# MAKER-UNO-X.net
KiCad netlist of a schematic drawn in EAGLE
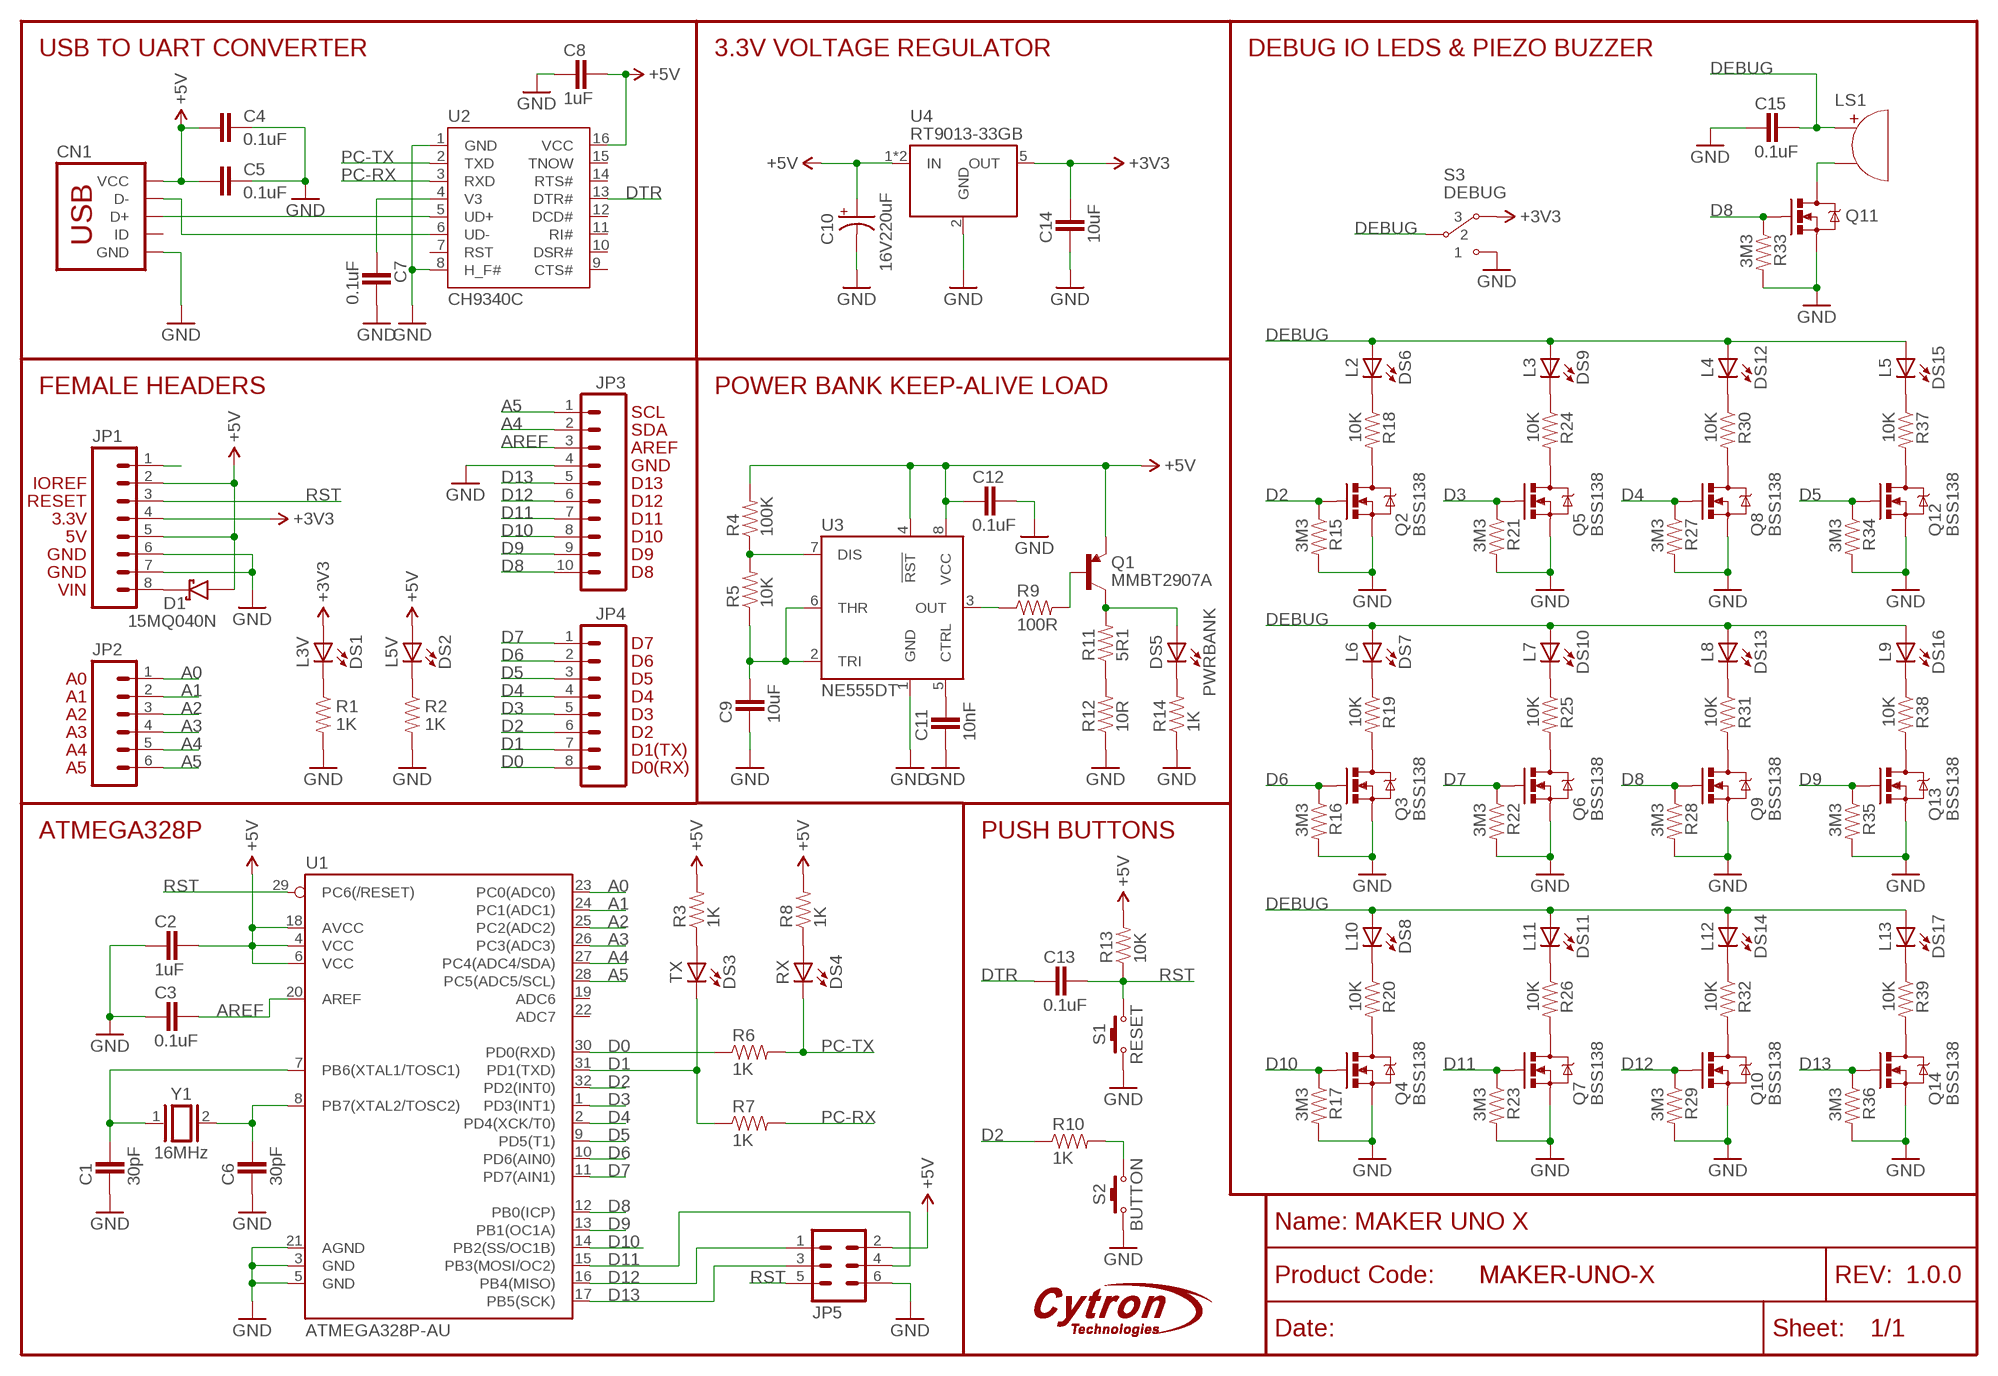
[diagram p0: schematic, sheet 1]

(export (version "E")
  (design (tool "Eeschema 10.0.6"))
  (components
    (comp (ref "C1")
      (value "30pF")
      (footprint "eagle-import:1608")
      (libsource (lib "eagle-import") (part "CAP-C_(1608)_30PF"))
    )
    (comp (ref "C2")
      (value "1uF")
      (footprint "eagle-import:1608")
      (libsource (lib "eagle-import") (part "CAP-C_(1608)_1UF"))
    )
    (comp (ref "C3")
      (value "0.1uF")
      (footprint "eagle-import:1608")
      (libsource (lib "eagle-import") (part "CAP-C_(1608)_0.1UF"))
    )
    (comp (ref "C4")
      (value "0.1uF")
      (footprint "eagle-import:1608")
      (libsource (lib "eagle-import") (part "CAP-C_(1608)_0.1UF"))
    )
    (comp (ref "C5")
      (value "0.1uF")
      (footprint "eagle-import:1608")
      (libsource (lib "eagle-import") (part "CAP-C_(1608)_0.1UF"))
    )
    (comp (ref "C6")
      (value "30pF")
      (footprint "eagle-import:1608")
      (libsource (lib "eagle-import") (part "CAP-C_(1608)_30PF"))
    )
    (comp (ref "C7")
      (value "0.1uF")
      (footprint "eagle-import:1608")
      (libsource (lib "eagle-import") (part "CAP-C_(1608)_0.1UF"))
    )
    (comp (ref "C8")
      (value "1uF")
      (footprint "eagle-import:1608")
      (libsource (lib "eagle-import") (part "CAP-C_(1608)_1UF"))
    )
    (comp (ref "C9")
      (value "10uF")
      (footprint "eagle-import:2012")
      (libsource (lib "eagle-import") (part "CAP-C_(2012)_10UF"))
    )
    (comp (ref "C10")
      (value "16V220uF")
      (footprint "eagle-import:ECAP-CHEMICON-F")
      (libsource (lib "eagle-import") (part "CAP-E-ALUMINIUM_(CHEMICON-F55)_16V220UF"))
    )
    (comp (ref "C11")
      (value "10nF")
      (footprint "eagle-import:1608")
      (libsource (lib "eagle-import") (part "CAP-C_(1608)_10NF"))
    )
    (comp (ref "C12")
      (value "0.1uF")
      (footprint "eagle-import:1608")
      (libsource (lib "eagle-import") (part "CAP-C_(1608)_0.1UF"))
    )
    (comp (ref "C13")
      (value "0.1uF")
      (footprint "eagle-import:1608")
      (libsource (lib "eagle-import") (part "CAP-C_(1608)_0.1UF"))
    )
    (comp (ref "C14")
      (value "10uF")
      (footprint "eagle-import:2012")
      (libsource (lib "eagle-import") (part "CAP-C_(2012)_10UF"))
    )
    (comp (ref "C15")
      (value "0.1uF")
      (footprint "eagle-import:1608")
      (libsource (lib "eagle-import") (part "CAP-C_(1608)_0.1UF"))
    )
    (comp (ref "CN1")
      (value "USB-5PIN_(MICRO-B-RA)")
      (footprint "eagle-import:USB-MICRO-B-REC")
      (libsource (lib "eagle-import") (part "USB-5PIN_(MICRO-B-RA)"))
    )
    (comp (ref "D1")
      (value "40V 3A")
      (footprint "eagle-import:D-SMA")
      (fields (field (name "MPN") "15MQ040N"))
      (libsource (lib "eagle-import") (part "DIODE-SCHOTTKY_(SMA)_15MQ040N"))
    )
    (comp (ref "DS1")
      (value "Green")
      (footprint "eagle-import:LED-1608")
      (fields (field (name "LABEL") "L3V"))
      (libsource (lib "eagle-import") (part "LED_(1608)_GREEN"))
    )
    (comp (ref "DS2")
      (value "Green")
      (footprint "eagle-import:LED-1608")
      (fields (field (name "LABEL") "L5V"))
      (libsource (lib "eagle-import") (part "LED_(1608)_GREEN"))
    )
    (comp (ref "DS3")
      (value "Red")
      (footprint "eagle-import:LED-1608")
      (fields (field (name "LABEL") "TX"))
      (libsource (lib "eagle-import") (part "LED_(1608)_RED"))
    )
    (comp (ref "DS4")
      (value "Yellow")
      (footprint "eagle-import:LED-1608")
      (fields (field (name "LABEL") "RX"))
      (libsource (lib "eagle-import") (part "LED_(1608)_YELLOW"))
    )
    (comp (ref "DS5")
      (value "Red")
      (footprint "eagle-import:LED-1608")
      (fields (field (name "LABEL") "PWRBANK"))
      (libsource (lib "eagle-import") (part "LED_(1608)_RED"))
    )
    (comp (ref "DS6")
      (value "Blue")
      (footprint "eagle-import:LED-1608")
      (fields (field (name "LABEL") "L2"))
      (libsource (lib "eagle-import") (part "LED_(1608)_BLUE"))
    )
    (comp (ref "DS7")
      (value "Blue")
      (footprint "eagle-import:LED-1608")
      (fields (field (name "LABEL") "L6"))
      (libsource (lib "eagle-import") (part "LED_(1608)_BLUE"))
    )
    (comp (ref "DS8")
      (value "Blue")
      (footprint "eagle-import:LED-1608")
      (fields (field (name "LABEL") "L10"))
      (libsource (lib "eagle-import") (part "LED_(1608)_BLUE"))
    )
    (comp (ref "DS9")
      (value "Blue")
      (footprint "eagle-import:LED-1608")
      (fields (field (name "LABEL") "L3"))
      (libsource (lib "eagle-import") (part "LED_(1608)_BLUE"))
    )
    (comp (ref "DS10")
      (value "Blue")
      (footprint "eagle-import:LED-1608")
      (fields (field (name "LABEL") "L7"))
      (libsource (lib "eagle-import") (part "LED_(1608)_BLUE"))
    )
    (comp (ref "DS11")
      (value "Blue")
      (footprint "eagle-import:LED-1608")
      (fields (field (name "LABEL") "L11"))
      (libsource (lib "eagle-import") (part "LED_(1608)_BLUE"))
    )
    (comp (ref "DS12")
      (value "Blue")
      (footprint "eagle-import:LED-1608")
      (fields (field (name "LABEL") "L4"))
      (libsource (lib "eagle-import") (part "LED_(1608)_BLUE"))
    )
    (comp (ref "DS13")
      (value "Blue")
      (footprint "eagle-import:LED-1608")
      (fields (field (name "LABEL") "L8"))
      (libsource (lib "eagle-import") (part "LED_(1608)_BLUE"))
    )
    (comp (ref "DS14")
      (value "Blue")
      (footprint "eagle-import:LED-1608")
      (fields (field (name "LABEL") "L12"))
      (libsource (lib "eagle-import") (part "LED_(1608)_BLUE"))
    )
    (comp (ref "DS15")
      (value "Blue")
      (footprint "eagle-import:LED-1608")
      (fields (field (name "LABEL") "L5"))
      (libsource (lib "eagle-import") (part "LED_(1608)_BLUE"))
    )
    (comp (ref "DS16")
      (value "Blue")
      (footprint "eagle-import:LED-1608")
      (fields (field (name "LABEL") "L9"))
      (libsource (lib "eagle-import") (part "LED_(1608)_BLUE"))
    )
    (comp (ref "DS17")
      (value "Blue")
      (footprint "eagle-import:LED-1608")
      (fields (field (name "LABEL") "L13"))
      (libsource (lib "eagle-import") (part "LED_(1608)_BLUE"))
    )
    (comp (ref "JP1")
      (value "8 Ways")
      (footprint "eagle-import:S-HDR-F1X08")
      (libsource (lib "eagle-import") (part "HEADER-1X08_(SMD-FEMALE-TYPE1)"))
    )
    (comp (ref "JP2")
      (value "6 Ways")
      (footprint "eagle-import:S-HDR-F1X06")
      (libsource (lib "eagle-import") (part "HEADER-1X06_(SMD-FEMALE-TYPE1)"))
    )
    (comp (ref "JP3")
      (value "10 Ways")
      (footprint "eagle-import:S-HDR-F1X10")
      (libsource (lib "eagle-import") (part "HEADER-1X10_(SMD-FEMALE-TYPE1)"))
    )
    (comp (ref "JP4")
      (value "8 Ways")
      (footprint "eagle-import:S-HDR-F1X08")
      (libsource (lib "eagle-import") (part "HEADER-1X08_(SMD-FEMALE-TYPE1)"))
    )
    (comp (ref "JP5")
      (value "2x3 Ways")
      (footprint "eagle-import:S-HDR-M2X03")
      (libsource (lib "eagle-import") (part "HEADER-2X03_(S-HDR-M2X03)"))
    )
    (comp (ref "LS1")
      (value "BUZZER_(8530)")
      (footprint "eagle-import:S-BUZZER-HXD-8530A-03627")
      (libsource (lib "eagle-import") (part "BUZZER_(8530)"))
    )
    (comp (ref "Q1")
      (value "60V 600mA")
      (footprint "eagle-import:SOT-23")
      (fields (field (name "MF") "CHANGJIANG") (field (name "MPN") "MMBT2907A"))
      (libsource (lib "eagle-import") (part "TRANSISTOR-PNP_(SOT-23-BEC)_MMBT2907"))
    )
    (comp (ref "Q2")
      (value "50V 220mA")
      (footprint "eagle-import:SOT-23")
      (fields (field (name "MPN") "BSS138"))
      (libsource (lib "eagle-import") (part "MOSFET-N_(SOT-23)_BSS138"))
    )
    (comp (ref "Q3")
      (value "50V 220mA")
      (footprint "eagle-import:SOT-23")
      (fields (field (name "MPN") "BSS138"))
      (libsource (lib "eagle-import") (part "MOSFET-N_(SOT-23)_BSS138"))
    )
    (comp (ref "Q4")
      (value "50V 220mA")
      (footprint "eagle-import:SOT-23")
      (fields (field (name "MPN") "BSS138"))
      (libsource (lib "eagle-import") (part "MOSFET-N_(SOT-23)_BSS138"))
    )
    (comp (ref "Q5")
      (value "50V 220mA")
      (footprint "eagle-import:SOT-23")
      (fields (field (name "MPN") "BSS138"))
      (libsource (lib "eagle-import") (part "MOSFET-N_(SOT-23)_BSS138"))
    )
    (comp (ref "Q6")
      (value "50V 220mA")
      (footprint "eagle-import:SOT-23")
      (fields (field (name "MPN") "BSS138"))
      (libsource (lib "eagle-import") (part "MOSFET-N_(SOT-23)_BSS138"))
    )
    (comp (ref "Q7")
      (value "50V 220mA")
      (footprint "eagle-import:SOT-23")
      (fields (field (name "MPN") "BSS138"))
      (libsource (lib "eagle-import") (part "MOSFET-N_(SOT-23)_BSS138"))
    )
    (comp (ref "Q8")
      (value "50V 220mA")
      (footprint "eagle-import:SOT-23")
      (fields (field (name "MPN") "BSS138"))
      (libsource (lib "eagle-import") (part "MOSFET-N_(SOT-23)_BSS138"))
    )
    (comp (ref "Q9")
      (value "50V 220mA")
      (footprint "eagle-import:SOT-23")
      (fields (field (name "MPN") "BSS138"))
      (libsource (lib "eagle-import") (part "MOSFET-N_(SOT-23)_BSS138"))
    )
    (comp (ref "Q10")
      (value "50V 220mA")
      (footprint "eagle-import:SOT-23")
      (fields (field (name "MPN") "BSS138"))
      (libsource (lib "eagle-import") (part "MOSFET-N_(SOT-23)_BSS138"))
    )
    (comp (ref "Q11")
      (value "50V 220mA")
      (footprint "eagle-import:SOT-23")
      (fields (field (name "MPN") "BSS138"))
      (libsource (lib "eagle-import") (part "MOSFET-N_(SOT-23)_BSS138"))
    )
    (comp (ref "Q12")
      (value "50V 220mA")
      (footprint "eagle-import:SOT-23")
      (fields (field (name "MPN") "BSS138"))
      (libsource (lib "eagle-import") (part "MOSFET-N_(SOT-23)_BSS138"))
    )
    (comp (ref "Q13")
      (value "50V 220mA")
      (footprint "eagle-import:SOT-23")
      (fields (field (name "MPN") "BSS138"))
      (libsource (lib "eagle-import") (part "MOSFET-N_(SOT-23)_BSS138"))
    )
    (comp (ref "Q14")
      (value "50V 220mA")
      (footprint "eagle-import:SOT-23")
      (fields (field (name "MPN") "BSS138"))
      (libsource (lib "eagle-import") (part "MOSFET-N_(SOT-23)_BSS138"))
    )
    (comp (ref "R1")
      (value "1K")
      (footprint "eagle-import:1608")
      (libsource (lib "eagle-import") (part "RESISTOR_(1608)_1K"))
    )
    (comp (ref "R2")
      (value "1K")
      (footprint "eagle-import:1608")
      (libsource (lib "eagle-import") (part "RESISTOR_(1608)_1K"))
    )
    (comp (ref "R3")
      (value "1K")
      (footprint "eagle-import:1608")
      (libsource (lib "eagle-import") (part "RESISTOR_(1608)_1K"))
    )
    (comp (ref "R4")
      (value "100K")
      (footprint "eagle-import:1608")
      (libsource (lib "eagle-import") (part "RESISTOR_(1608)_100K"))
    )
    (comp (ref "R5")
      (value "10K")
      (footprint "eagle-import:1608")
      (libsource (lib "eagle-import") (part "RESISTOR_(1608)_10K"))
    )
    (comp (ref "R6")
      (value "1K")
      (footprint "eagle-import:1608")
      (libsource (lib "eagle-import") (part "RESISTOR_(1608)_1K"))
    )
    (comp (ref "R7")
      (value "1K")
      (footprint "eagle-import:1608")
      (libsource (lib "eagle-import") (part "RESISTOR_(1608)_1K"))
    )
    (comp (ref "R8")
      (value "1K")
      (footprint "eagle-import:1608")
      (libsource (lib "eagle-import") (part "RESISTOR_(1608)_1K"))
    )
    (comp (ref "R9")
      (value "100R")
      (footprint "eagle-import:1608")
      (libsource (lib "eagle-import") (part "RESISTOR_(1608)_100R"))
    )
    (comp (ref "R10")
      (value "1K")
      (footprint "eagle-import:1608")
      (libsource (lib "eagle-import") (part "RESISTOR_(1608)_1K"))
    )
    (comp (ref "R11")
      (value "5R1")
      (footprint "eagle-import:2012")
      (libsource (lib "eagle-import") (part "RESISTOR_(2012)_5R1"))
    )
    (comp (ref "R12")
      (value "10R")
      (footprint "eagle-import:2012")
      (libsource (lib "eagle-import") (part "RESISTOR_(2012)_10R"))
    )
    (comp (ref "R13")
      (value "10K")
      (footprint "eagle-import:1608")
      (libsource (lib "eagle-import") (part "RESISTOR_(1608)_10K"))
    )
    (comp (ref "R14")
      (value "1K")
      (footprint "eagle-import:1608")
      (libsource (lib "eagle-import") (part "RESISTOR_(1608)_1K"))
    )
    (comp (ref "R15")
      (value "3M3")
      (footprint "eagle-import:1608")
      (libsource (lib "eagle-import") (part "RESISTOR_(1608)_3M3"))
    )
    (comp (ref "R16")
      (value "3M3")
      (footprint "eagle-import:1608")
      (libsource (lib "eagle-import") (part "RESISTOR_(1608)_3M3"))
    )
    (comp (ref "R17")
      (value "3M3")
      (footprint "eagle-import:1608")
      (libsource (lib "eagle-import") (part "RESISTOR_(1608)_3M3"))
    )
    (comp (ref "R18")
      (value "10K")
      (footprint "eagle-import:1608")
      (libsource (lib "eagle-import") (part "RESISTOR_(1608)_10K"))
    )
    (comp (ref "R19")
      (value "10K")
      (footprint "eagle-import:1608")
      (libsource (lib "eagle-import") (part "RESISTOR_(1608)_10K"))
    )
    (comp (ref "R20")
      (value "10K")
      (footprint "eagle-import:1608")
      (libsource (lib "eagle-import") (part "RESISTOR_(1608)_10K"))
    )
    (comp (ref "R21")
      (value "3M3")
      (footprint "eagle-import:1608")
      (libsource (lib "eagle-import") (part "RESISTOR_(1608)_3M3"))
    )
    (comp (ref "R22")
      (value "3M3")
      (footprint "eagle-import:1608")
      (libsource (lib "eagle-import") (part "RESISTOR_(1608)_3M3"))
    )
    (comp (ref "R23")
      (value "3M3")
      (footprint "eagle-import:1608")
      (libsource (lib "eagle-import") (part "RESISTOR_(1608)_3M3"))
    )
    (comp (ref "R24")
      (value "10K")
      (footprint "eagle-import:1608")
      (libsource (lib "eagle-import") (part "RESISTOR_(1608)_10K"))
    )
    (comp (ref "R25")
      (value "10K")
      (footprint "eagle-import:1608")
      (libsource (lib "eagle-import") (part "RESISTOR_(1608)_10K"))
    )
    (comp (ref "R26")
      (value "10K")
      (footprint "eagle-import:1608")
      (libsource (lib "eagle-import") (part "RESISTOR_(1608)_10K"))
    )
    (comp (ref "R27")
      (value "3M3")
      (footprint "eagle-import:1608")
      (libsource (lib "eagle-import") (part "RESISTOR_(1608)_3M3"))
    )
    (comp (ref "R28")
      (value "3M3")
      (footprint "eagle-import:1608")
      (libsource (lib "eagle-import") (part "RESISTOR_(1608)_3M3"))
    )
    (comp (ref "R29")
      (value "3M3")
      (footprint "eagle-import:1608")
      (libsource (lib "eagle-import") (part "RESISTOR_(1608)_3M3"))
    )
    (comp (ref "R30")
      (value "10K")
      (footprint "eagle-import:1608")
      (libsource (lib "eagle-import") (part "RESISTOR_(1608)_10K"))
    )
    (comp (ref "R31")
      (value "10K")
      (footprint "eagle-import:1608")
      (libsource (lib "eagle-import") (part "RESISTOR_(1608)_10K"))
    )
    (comp (ref "R32")
      (value "10K")
      (footprint "eagle-import:1608")
      (libsource (lib "eagle-import") (part "RESISTOR_(1608)_10K"))
    )
    (comp (ref "R33")
      (value "3M3")
      (footprint "eagle-import:1608")
      (libsource (lib "eagle-import") (part "RESISTOR_(1608)_3M3"))
    )
    (comp (ref "R34")
      (value "3M3")
      (footprint "eagle-import:1608")
      (libsource (lib "eagle-import") (part "RESISTOR_(1608)_3M3"))
    )
    (comp (ref "R35")
      (value "3M3")
      (footprint "eagle-import:1608")
      (libsource (lib "eagle-import") (part "RESISTOR_(1608)_3M3"))
    )
    (comp (ref "R36")
      (value "3M3")
      (footprint "eagle-import:1608")
      (libsource (lib "eagle-import") (part "RESISTOR_(1608)_3M3"))
    )
    (comp (ref "R37")
      (value "10K")
      (footprint "eagle-import:1608")
      (libsource (lib "eagle-import") (part "RESISTOR_(1608)_10K"))
    )
    (comp (ref "R38")
      (value "10K")
      (footprint "eagle-import:1608")
      (libsource (lib "eagle-import") (part "RESISTOR_(1608)_10K"))
    )
    (comp (ref "R39")
      (value "10K")
      (footprint "eagle-import:1608")
      (libsource (lib "eagle-import") (part "RESISTOR_(1608)_10K"))
    )
    (comp (ref "S1")
      (value "SW-PB_(KAN3246)")
      (footprint "eagle-import:SW-PB-KAN3246")
      (fields (field (name "LABEL") "RESET"))
      (libsource (lib "eagle-import") (part "SW-PB_(KAN3246)"))
    )
    (comp (ref "S2")
      (value "SW-PB_(KAN3246)")
      (footprint "eagle-import:SW-PB-KAN3246")
      (fields (field (name "LABEL") "BUTTON"))
      (libsource (lib "eagle-import") (part "SW-PB_(KAN3246)"))
    )
    (comp (ref "S3")
      (value "SW-SLIDE-SPDT_(SMD)")
      (footprint "eagle-import:SW-SLIDE-SPDT-SMD")
      (fields (field (name "LABEL") "DEBUG"))
      (libsource (lib "eagle-import") (part "SW-SLIDE-SPDT_(SMD)"))
    )
    (comp (ref "U1")
      (value "ATMEGA328_SMT")
      (footprint "eagle-import:TQFP-32-08")
      (fields (field (name "MPN") "ATMEGA328P-AU") (field (name "MF") "ATMEL"))
      (libsource (lib "eagle-import") (part "ATMEGA328_SMT"))
    )
    (comp (ref "U2")
      (value "CH9340C")
      (footprint "eagle-import:SOIC-16N")
      (fields (field (name "MF") "WCH"))
      (libsource (lib "eagle-import") (part "CH9340C"))
    )
    (comp (ref "U3")
      (value "555_(SOIC-08N)")
      (footprint "eagle-import:SOIC-08N")
      (fields (field (name "MPN") "NE555DT") (field (name "MF") "STMicroelectronics"))
      (libsource (lib "eagle-import") (part "555_(SOIC-08N)"))
    )
    (comp (ref "U4")
      (value "3.3V 500mA")
      (footprint "eagle-import:SOT-23-5")
      (fields (field (name "MF") "RICHTEK") (field (name "MPN") "RT9013-33GB"))
      (libsource (lib "eagle-import") (part "VREG_(SOT-23-5)_RT9013-33GB"))
    )
    (comp (ref "Y1")
      (value "16MHz")
      (footprint "eagle-import:XTAL-HC49UP")
      (fields (field (name "MF") "TXC") (field (name "MPN") "9C16000001"))
      (libsource (lib "eagle-import") (part "XTAL_(SMD-HC49UP)_16MHZ"))
    )
  )
  (nets
    (net (code "1") (name "+3V3") (class "Default")
      (node (ref "C14") (pin "1") (pinfunction "1_1") (pintype "passive"))
      (node (ref "DS1") (pin "A") (pinfunction "A_A") (pintype "bidirectional"))
      (node (ref "JP1") (pin "4") (pinfunction "4_4") (pintype "passive"))
      (node (ref "S3") (pin "3") (pinfunction "3_3") (pintype "bidirectional"))
      (node (ref "U4") (pin "5") (pinfunction "OUT_5") (pintype "bidirectional"))
    )
    (net (code "2") (name "+5V") (class "Default")
      (node (ref "C10") (pin "+") (pinfunction "+_+") (pintype "passive"))
      (node (ref "C12") (pin "2") (pinfunction "2_2") (pintype "passive"))
      (node (ref "C2") (pin "1") (pinfunction "1_1") (pintype "passive"))
      (node (ref "C4") (pin "1") (pinfunction "1_1") (pintype "passive"))
      (node (ref "C5") (pin "1") (pinfunction "1_1") (pintype "passive"))
      (node (ref "C8") (pin "1") (pinfunction "1_1") (pintype "passive"))
      (node (ref "CN1") (pin "VBUS1") (pinfunction "VCC_VBUS1") (pintype "passive"))
      (node (ref "D1") (pin "A") (pinfunction "A_A") (pintype "bidirectional"))
      (node (ref "DS2") (pin "A") (pinfunction "A_A") (pintype "bidirectional"))
      (node (ref "JP1") (pin "2") (pinfunction "2_2") (pintype "passive"))
      (node (ref "JP1") (pin "5") (pinfunction "5_5") (pintype "passive"))
      (node (ref "JP5") (pin "2") (pinfunction "2_2") (pintype "passive"))
      (node (ref "Q1") (pin "2") (pinfunction "E_2") (pintype "bidirectional"))
      (node (ref "R13") (pin "2") (pinfunction "2_2") (pintype "passive"))
      (node (ref "R3") (pin "2") (pinfunction "2_2") (pintype "passive"))
      (node (ref "R4") (pin "2") (pinfunction "2_2") (pintype "passive"))
      (node (ref "R8") (pin "2") (pinfunction "2_2") (pintype "passive"))
      (node (ref "U1") (pin "18") (pinfunction "AVCC_18") (pintype "bidirectional"))
      (node (ref "U1") (pin "4") (pinfunction "VCC_4") (pintype "bidirectional"))
      (node (ref "U1") (pin "6") (pinfunction "VCC_6") (pintype "bidirectional"))
      (node (ref "U2") (pin "16") (pinfunction "VCC_16") (pintype "power_in"))
      (node (ref "U3") (pin "4") (pinfunction "~{RST}_4") (pintype "bidirectional"))
      (node (ref "U3") (pin "8") (pinfunction "VCC_8") (pintype "bidirectional"))
      (node (ref "U4") (pin "1") (pinfunction "IN_1") (pintype "input"))
      (node (ref "U4") (pin "3") (pinfunction "IN_3") (pintype "input"))
    )
    (net (code "3") (name "/A0") (class "Default")
      (node (ref "JP2") (pin "1") (pinfunction "1_1") (pintype "passive"))
      (node (ref "U1") (pin "23") (pinfunction "PC0(ADC0)_23") (pintype "bidirectional"))
    )
    (net (code "4") (name "/A1") (class "Default")
      (node (ref "JP2") (pin "2") (pinfunction "2_2") (pintype "passive"))
      (node (ref "U1") (pin "24") (pinfunction "PC1(ADC1)_24") (pintype "bidirectional"))
    )
    (net (code "5") (name "/A2") (class "Default")
      (node (ref "JP2") (pin "3") (pinfunction "3_3") (pintype "passive"))
      (node (ref "U1") (pin "25") (pinfunction "PC2(ADC2)_25") (pintype "bidirectional"))
    )
    (net (code "6") (name "/A3") (class "Default")
      (node (ref "JP2") (pin "4") (pinfunction "4_4") (pintype "passive"))
      (node (ref "U1") (pin "26") (pinfunction "PC3(ADC3)_26") (pintype "bidirectional"))
    )
    (net (code "7") (name "/A4") (class "Default")
      (node (ref "JP2") (pin "5") (pinfunction "5_5") (pintype "passive"))
      (node (ref "JP3") (pin "2") (pinfunction "2_2") (pintype "passive"))
      (node (ref "U1") (pin "27") (pinfunction "PC4(ADC4/SDA)_27") (pintype "bidirectional"))
    )
    (net (code "8") (name "/A5") (class "Default")
      (node (ref "JP2") (pin "6") (pinfunction "6_6") (pintype "passive"))
      (node (ref "JP3") (pin "1") (pinfunction "1_1") (pintype "passive"))
      (node (ref "U1") (pin "28") (pinfunction "PC5(ADC5/SCL)_28") (pintype "bidirectional"))
    )
    (net (code "9") (name "/AREF") (class "Default")
      (node (ref "C3") (pin "1") (pinfunction "1_1") (pintype "passive"))
      (node (ref "JP3") (pin "3") (pinfunction "3_3") (pintype "passive"))
      (node (ref "U1") (pin "20") (pinfunction "AREF_20") (pintype "bidirectional"))
    )
    (net (code "10") (name "/D0") (class "Default")
      (node (ref "JP4") (pin "8") (pinfunction "8_8") (pintype "passive"))
      (node (ref "R6") (pin "1") (pinfunction "1_1") (pintype "passive"))
      (node (ref "U1") (pin "30") (pinfunction "PD0(RXD)_30") (pintype "bidirectional"))
    )
    (net (code "11") (name "/D1") (class "Default")
      (node (ref "DS3") (pin "C") (pinfunction "C_C") (pintype "bidirectional"))
      (node (ref "JP4") (pin "7") (pinfunction "7_7") (pintype "passive"))
      (node (ref "R7") (pin "1") (pinfunction "1_1") (pintype "passive"))
      (node (ref "U1") (pin "31") (pinfunction "PD1(TXD)_31") (pintype "bidirectional"))
    )
    (net (code "12") (name "/D2") (class "Default")
      (node (ref "JP4") (pin "6") (pinfunction "6_6") (pintype "passive"))
      (node (ref "Q2") (pin "1") (pinfunction "G_1") (pintype "input"))
      (node (ref "R10") (pin "1") (pinfunction "1_1") (pintype "passive"))
      (node (ref "R15") (pin "1") (pinfunction "1_1") (pintype "passive"))
      (node (ref "U1") (pin "32") (pinfunction "PD2(INT0)_32") (pintype "bidirectional"))
    )
    (net (code "13") (name "/D3") (class "Default")
      (node (ref "JP4") (pin "5") (pinfunction "5_5") (pintype "passive"))
      (node (ref "Q5") (pin "1") (pinfunction "G_1") (pintype "input"))
      (node (ref "R21") (pin "1") (pinfunction "1_1") (pintype "passive"))
      (node (ref "U1") (pin "1") (pinfunction "PD3(INT1)_1") (pintype "bidirectional"))
    )
    (net (code "14") (name "/D4") (class "Default")
      (node (ref "JP4") (pin "4") (pinfunction "4_4") (pintype "passive"))
      (node (ref "Q8") (pin "1") (pinfunction "G_1") (pintype "input"))
      (node (ref "R27") (pin "1") (pinfunction "1_1") (pintype "passive"))
      (node (ref "U1") (pin "2") (pinfunction "PD4(XCK/T0)_2") (pintype "bidirectional"))
    )
    (net (code "15") (name "/D5") (class "Default")
      (node (ref "JP4") (pin "3") (pinfunction "3_3") (pintype "passive"))
      (node (ref "Q12") (pin "1") (pinfunction "G_1") (pintype "input"))
      (node (ref "R34") (pin "1") (pinfunction "1_1") (pintype "passive"))
      (node (ref "U1") (pin "9") (pinfunction "PD5(T1)_9") (pintype "bidirectional"))
    )
    (net (code "16") (name "/D6") (class "Default")
      (node (ref "JP4") (pin "2") (pinfunction "2_2") (pintype "passive"))
      (node (ref "Q3") (pin "1") (pinfunction "G_1") (pintype "input"))
      (node (ref "R16") (pin "1") (pinfunction "1_1") (pintype "passive"))
      (node (ref "U1") (pin "10") (pinfunction "PD6(AIN0)_10") (pintype "bidirectional"))
    )
    (net (code "17") (name "/D7") (class "Default")
      (node (ref "JP4") (pin "1") (pinfunction "1_1") (pintype "passive"))
      (node (ref "Q6") (pin "1") (pinfunction "G_1") (pintype "input"))
      (node (ref "R22") (pin "1") (pinfunction "1_1") (pintype "passive"))
      (node (ref "U1") (pin "11") (pinfunction "PD7(AIN1)_11") (pintype "bidirectional"))
    )
    (net (code "18") (name "/D8") (class "Default")
      (node (ref "JP3") (pin "10") (pinfunction "10_10") (pintype "passive"))
      (node (ref "Q11") (pin "1") (pinfunction "G_1") (pintype "input"))
      (node (ref "Q9") (pin "1") (pinfunction "G_1") (pintype "input"))
      (node (ref "R28") (pin "1") (pinfunction "1_1") (pintype "passive"))
      (node (ref "R33") (pin "1") (pinfunction "1_1") (pintype "passive"))
      (node (ref "U1") (pin "12") (pinfunction "PB0(ICP)_12") (pintype "bidirectional"))
    )
    (net (code "19") (name "/D9") (class "Default")
      (node (ref "JP3") (pin "9") (pinfunction "9_9") (pintype "passive"))
      (node (ref "Q13") (pin "1") (pinfunction "G_1") (pintype "input"))
      (node (ref "R35") (pin "1") (pinfunction "1_1") (pintype "passive"))
      (node (ref "U1") (pin "13") (pinfunction "PB1(OC1A)_13") (pintype "bidirectional"))
    )
    (net (code "20") (name "/D10") (class "Default")
      (node (ref "JP3") (pin "8") (pinfunction "8_8") (pintype "passive"))
      (node (ref "Q4") (pin "1") (pinfunction "G_1") (pintype "input"))
      (node (ref "R17") (pin "1") (pinfunction "1_1") (pintype "passive"))
      (node (ref "U1") (pin "14") (pinfunction "PB2(SS/OC1B)_14") (pintype "bidirectional"))
    )
    (net (code "21") (name "/D11") (class "Default")
      (node (ref "JP3") (pin "7") (pinfunction "7_7") (pintype "passive"))
      (node (ref "JP5") (pin "4") (pinfunction "4_4") (pintype "passive"))
      (node (ref "Q7") (pin "1") (pinfunction "G_1") (pintype "input"))
      (node (ref "R23") (pin "1") (pinfunction "1_1") (pintype "passive"))
      (node (ref "U1") (pin "15") (pinfunction "PB3(MOSI/OC2)_15") (pintype "bidirectional"))
    )
    (net (code "22") (name "/D12") (class "Default")
      (node (ref "JP3") (pin "6") (pinfunction "6_6") (pintype "passive"))
      (node (ref "JP5") (pin "1") (pinfunction "1_1") (pintype "passive"))
      (node (ref "Q10") (pin "1") (pinfunction "G_1") (pintype "input"))
      (node (ref "R29") (pin "1") (pinfunction "1_1") (pintype "passive"))
      (node (ref "U1") (pin "16") (pinfunction "PB4(MISO)_16") (pintype "bidirectional"))
    )
    (net (code "23") (name "/D13") (class "Default")
      (node (ref "JP3") (pin "5") (pinfunction "5_5") (pintype "passive"))
      (node (ref "JP5") (pin "3") (pinfunction "3_3") (pintype "passive"))
      (node (ref "Q14") (pin "1") (pinfunction "G_1") (pintype "input"))
      (node (ref "R36") (pin "1") (pinfunction "1_1") (pintype "passive"))
      (node (ref "U1") (pin "17") (pinfunction "PB5(SCK)_17") (pintype "bidirectional"))
    )
    (net (code "24") (name "/DEBUG") (class "Default")
      (node (ref "C15") (pin "1") (pinfunction "1_1") (pintype "passive"))
      (node (ref "DS10") (pin "A") (pinfunction "A_A") (pintype "bidirectional"))
      (node (ref "DS11") (pin "A") (pinfunction "A_A") (pintype "bidirectional"))
      (node (ref "DS12") (pin "A") (pinfunction "A_A") (pintype "bidirectional"))
      (node (ref "DS13") (pin "A") (pinfunction "A_A") (pintype "bidirectional"))
      (node (ref "DS14") (pin "A") (pinfunction "A_A") (pintype "bidirectional"))
      (node (ref "DS15") (pin "A") (pinfunction "A_A") (pintype "bidirectional"))
      (node (ref "DS16") (pin "A") (pinfunction "A_A") (pintype "bidirectional"))
      (node (ref "DS17") (pin "A") (pinfunction "A_A") (pintype "bidirectional"))
      (node (ref "DS6") (pin "A") (pinfunction "A_A") (pintype "bidirectional"))
      (node (ref "DS7") (pin "A") (pinfunction "A_A") (pintype "bidirectional"))
      (node (ref "DS8") (pin "A") (pinfunction "A_A") (pintype "bidirectional"))
      (node (ref "DS9") (pin "A") (pinfunction "A_A") (pintype "bidirectional"))
      (node (ref "LS1") (pin "+") (pinfunction "+_+") (pintype "bidirectional"))
      (node (ref "S3") (pin "2") (pinfunction "2_2") (pintype "bidirectional"))
    )
    (net (code "25") (name "/DTR") (class "Default")
      (node (ref "C13") (pin "2") (pinfunction "2_2") (pintype "passive"))
      (node (ref "U2") (pin "13") (pinfunction "DTR#_13") (pintype "bidirectional"))
    )
    (net (code "26") (name "/PC-RX") (class "Default")
      (node (ref "R7") (pin "2") (pinfunction "2_2") (pintype "passive"))
      (node (ref "U2") (pin "3") (pinfunction "RXD_3") (pintype "bidirectional"))
    )
    (net (code "27") (name "/PC-TX") (class "Default")
      (node (ref "DS4") (pin "C") (pinfunction "C_C") (pintype "bidirectional"))
      (node (ref "R6") (pin "2") (pinfunction "2_2") (pintype "passive"))
      (node (ref "U2") (pin "2") (pinfunction "TXD_2") (pintype "bidirectional"))
    )
    (net (code "28") (name "/RST") (class "Default")
      (node (ref "C13") (pin "1") (pinfunction "1_1") (pintype "passive"))
      (node (ref "JP1") (pin "3") (pinfunction "3_3") (pintype "passive"))
      (node (ref "JP5") (pin "5") (pinfunction "5_5") (pintype "passive"))
      (node (ref "R13") (pin "1") (pinfunction "1_1") (pintype "passive"))
      (node (ref "S1") (pin "3") (pinfunction "2_3") (pintype "passive"))
      (node (ref "S1") (pin "4") (pinfunction "2_4") (pintype "passive"))
      (node (ref "U1") (pin "29") (pinfunction "PC6(/RESET)_29") (pintype "bidirectional"))
    )
    (net (code "29") (name "GND") (class "Default")
      (node (ref "C1") (pin "2") (pinfunction "2_2") (pintype "passive"))
      (node (ref "C10") (pin "-") (pinfunction "-_-") (pintype "passive"))
      (node (ref "C11") (pin "2") (pinfunction "2_2") (pintype "passive"))
      (node (ref "C12") (pin "1") (pinfunction "1_1") (pintype "passive"))
      (node (ref "C14") (pin "2") (pinfunction "2_2") (pintype "passive"))
      (node (ref "C15") (pin "2") (pinfunction "2_2") (pintype "passive"))
      (node (ref "C2") (pin "2") (pinfunction "2_2") (pintype "passive"))
      (node (ref "C3") (pin "2") (pinfunction "2_2") (pintype "passive"))
      (node (ref "C4") (pin "2") (pinfunction "2_2") (pintype "passive"))
      (node (ref "C5") (pin "2") (pinfunction "2_2") (pintype "passive"))
      (node (ref "C6") (pin "2") (pinfunction "2_2") (pintype "passive"))
      (node (ref "C7") (pin "1") (pinfunction "1_1") (pintype "passive"))
      (node (ref "C8") (pin "2") (pinfunction "2_2") (pintype "passive"))
      (node (ref "C9") (pin "2") (pinfunction "2_2") (pintype "passive"))
      (node (ref "CN1") (pin "GND1") (pinfunction "GND_GND1") (pintype "passive"))
      (node (ref "JP1") (pin "6") (pinfunction "6_6") (pintype "passive"))
      (node (ref "JP1") (pin "7") (pinfunction "7_7") (pintype "passive"))
      (node (ref "JP3") (pin "4") (pinfunction "4_4") (pintype "passive"))
      (node (ref "JP5") (pin "6") (pinfunction "6_6") (pintype "passive"))
      (node (ref "Q10") (pin "2") (pinfunction "S_2") (pintype "bidirectional"))
      (node (ref "Q11") (pin "2") (pinfunction "S_2") (pintype "bidirectional"))
      (node (ref "Q12") (pin "2") (pinfunction "S_2") (pintype "bidirectional"))
      (node (ref "Q13") (pin "2") (pinfunction "S_2") (pintype "bidirectional"))
      (node (ref "Q14") (pin "2") (pinfunction "S_2") (pintype "bidirectional"))
      (node (ref "Q2") (pin "2") (pinfunction "S_2") (pintype "bidirectional"))
      (node (ref "Q3") (pin "2") (pinfunction "S_2") (pintype "bidirectional"))
      (node (ref "Q4") (pin "2") (pinfunction "S_2") (pintype "bidirectional"))
      (node (ref "Q5") (pin "2") (pinfunction "S_2") (pintype "bidirectional"))
      (node (ref "Q6") (pin "2") (pinfunction "S_2") (pintype "bidirectional"))
      (node (ref "Q7") (pin "2") (pinfunction "S_2") (pintype "bidirectional"))
      (node (ref "Q8") (pin "2") (pinfunction "S_2") (pintype "bidirectional"))
      (node (ref "Q9") (pin "2") (pinfunction "S_2") (pintype "bidirectional"))
      (node (ref "R1") (pin "2") (pinfunction "2_2") (pintype "passive"))
      (node (ref "R12") (pin "1") (pinfunction "1_1") (pintype "passive"))
      (node (ref "R14") (pin "1") (pinfunction "1_1") (pintype "passive"))
      (node (ref "R15") (pin "2") (pinfunction "2_2") (pintype "passive"))
      (node (ref "R16") (pin "2") (pinfunction "2_2") (pintype "passive"))
      (node (ref "R17") (pin "2") (pinfunction "2_2") (pintype "passive"))
      (node (ref "R2") (pin "2") (pinfunction "2_2") (pintype "passive"))
      (node (ref "R21") (pin "2") (pinfunction "2_2") (pintype "passive"))
      (node (ref "R22") (pin "2") (pinfunction "2_2") (pintype "passive"))
      (node (ref "R23") (pin "2") (pinfunction "2_2") (pintype "passive"))
      (node (ref "R27") (pin "2") (pinfunction "2_2") (pintype "passive"))
      (node (ref "R28") (pin "2") (pinfunction "2_2") (pintype "passive"))
      (node (ref "R29") (pin "2") (pinfunction "2_2") (pintype "passive"))
      (node (ref "R33") (pin "2") (pinfunction "2_2") (pintype "passive"))
      (node (ref "R34") (pin "2") (pinfunction "2_2") (pintype "passive"))
      (node (ref "R35") (pin "2") (pinfunction "2_2") (pintype "passive"))
      (node (ref "R36") (pin "2") (pinfunction "2_2") (pintype "passive"))
      (node (ref "S1") (pin "1") (pinfunction "1_1") (pintype "passive"))
      (node (ref "S1") (pin "2") (pinfunction "1_2") (pintype "passive"))
      (node (ref "S2") (pin "1") (pinfunction "1_1") (pintype "passive"))
      (node (ref "S2") (pin "2") (pinfunction "1_2") (pintype "passive"))
      (node (ref "S3") (pin "1") (pinfunction "1_1") (pintype "bidirectional"))
      (node (ref "U1") (pin "21") (pinfunction "AGND_21") (pintype "bidirectional"))
      (node (ref "U1") (pin "3") (pinfunction "GND_3") (pintype "bidirectional"))
      (node (ref "U1") (pin "5") (pinfunction "GND_5") (pintype "bidirectional"))
      (node (ref "U2") (pin "1") (pinfunction "GND_1") (pintype "power_in"))
      (node (ref "U2") (pin "8") (pinfunction "H_F#_8") (pintype "bidirectional"))
      (node (ref "U3") (pin "1") (pinfunction "GND_1") (pintype "bidirectional"))
      (node (ref "U4") (pin "2") (pinfunction "GND_2") (pintype "bidirectional"))
    )
    (net (code "30") (name "Net-(CN1-D+)") (class "Default")
      (node (ref "CN1") (pin "D+1") (pinfunction "D+_D+1") (pintype "passive"))
      (node (ref "U2") (pin "5") (pinfunction "UD+_5") (pintype "bidirectional"))
    )
    (net (code "31") (name "Net-(CN1-D-)") (class "Default")
      (node (ref "CN1") (pin "D-1") (pinfunction "D-_D-1") (pintype "passive"))
      (node (ref "U2") (pin "6") (pinfunction "UD-_6") (pintype "bidirectional"))
    )
    (net (code "32") (name "Net-(D1-PadC)") (class "Default")
      (node (ref "D1") (pin "C") (pinfunction "C_C") (pintype "bidirectional"))
      (node (ref "JP1") (pin "8") (pinfunction "8_8") (pintype "passive"))
    )
    (net (code "33") (name "Net-(DS1-PadC)") (class "Default")
      (node (ref "DS1") (pin "C") (pinfunction "C_C") (pintype "bidirectional"))
      (node (ref "R1") (pin "1") (pinfunction "1_1") (pintype "passive"))
    )
    (net (code "34") (name "Net-(DS2-PadC)") (class "Default")
      (node (ref "DS2") (pin "C") (pinfunction "C_C") (pintype "bidirectional"))
      (node (ref "R2") (pin "1") (pinfunction "1_1") (pintype "passive"))
    )
    (net (code "35") (name "Net-(DS3-PadA)") (class "Default")
      (node (ref "DS3") (pin "A") (pinfunction "A_A") (pintype "bidirectional"))
      (node (ref "R3") (pin "1") (pinfunction "1_1") (pintype "passive"))
    )
    (net (code "36") (name "Net-(DS4-PadA)") (class "Default")
      (node (ref "DS4") (pin "A") (pinfunction "A_A") (pintype "bidirectional"))
      (node (ref "R8") (pin "1") (pinfunction "1_1") (pintype "passive"))
    )
    (net (code "37") (name "Net-(DS5-PadC)") (class "Default")
      (node (ref "DS5") (pin "C") (pinfunction "C_C") (pintype "bidirectional"))
      (node (ref "R14") (pin "2") (pinfunction "2_2") (pintype "passive"))
    )
    (net (code "38") (name "Net-(DS6-PadC)") (class "Default")
      (node (ref "DS6") (pin "C") (pinfunction "C_C") (pintype "bidirectional"))
      (node (ref "R18") (pin "1") (pinfunction "1_1") (pintype "passive"))
    )
    (net (code "39") (name "Net-(DS7-PadC)") (class "Default")
      (node (ref "DS7") (pin "C") (pinfunction "C_C") (pintype "bidirectional"))
      (node (ref "R19") (pin "1") (pinfunction "1_1") (pintype "passive"))
    )
    (net (code "40") (name "Net-(DS8-PadC)") (class "Default")
      (node (ref "DS8") (pin "C") (pinfunction "C_C") (pintype "bidirectional"))
      (node (ref "R20") (pin "1") (pinfunction "1_1") (pintype "passive"))
    )
    (net (code "41") (name "Net-(DS9-PadC)") (class "Default")
      (node (ref "DS9") (pin "C") (pinfunction "C_C") (pintype "bidirectional"))
      (node (ref "R24") (pin "1") (pinfunction "1_1") (pintype "passive"))
    )
    (net (code "42") (name "Net-(DS10-PadC)") (class "Default")
      (node (ref "DS10") (pin "C") (pinfunction "C_C") (pintype "bidirectional"))
      (node (ref "R25") (pin "1") (pinfunction "1_1") (pintype "passive"))
    )
    (net (code "43") (name "Net-(DS11-PadC)") (class "Default")
      (node (ref "DS11") (pin "C") (pinfunction "C_C") (pintype "bidirectional"))
      (node (ref "R26") (pin "1") (pinfunction "1_1") (pintype "passive"))
    )
    (net (code "44") (name "Net-(DS12-PadC)") (class "Default")
      (node (ref "DS12") (pin "C") (pinfunction "C_C") (pintype "bidirectional"))
      (node (ref "R30") (pin "1") (pinfunction "1_1") (pintype "passive"))
    )
    (net (code "45") (name "Net-(DS13-PadC)") (class "Default")
      (node (ref "DS13") (pin "C") (pinfunction "C_C") (pintype "bidirectional"))
      (node (ref "R31") (pin "1") (pinfunction "1_1") (pintype "passive"))
    )
    (net (code "46") (name "Net-(DS14-PadC)") (class "Default")
      (node (ref "DS14") (pin "C") (pinfunction "C_C") (pintype "bidirectional"))
      (node (ref "R32") (pin "1") (pinfunction "1_1") (pintype "passive"))
    )
    (net (code "47") (name "Net-(DS15-PadC)") (class "Default")
      (node (ref "DS15") (pin "C") (pinfunction "C_C") (pintype "bidirectional"))
      (node (ref "R37") (pin "1") (pinfunction "1_1") (pintype "passive"))
    )
    (net (code "48") (name "Net-(DS16-PadC)") (class "Default")
      (node (ref "DS16") (pin "C") (pinfunction "C_C") (pintype "bidirectional"))
      (node (ref "R38") (pin "1") (pinfunction "1_1") (pintype "passive"))
    )
    (net (code "49") (name "Net-(DS17-PadC)") (class "Default")
      (node (ref "DS17") (pin "C") (pinfunction "C_C") (pintype "bidirectional"))
      (node (ref "R39") (pin "1") (pinfunction "1_1") (pintype "passive"))
    )
    (net (code "50") (name "Net-(Q1-B)") (class "Default")
      (node (ref "Q1") (pin "1") (pinfunction "B_1") (pintype "input"))
      (node (ref "R9") (pin "2") (pinfunction "2_2") (pintype "passive"))
    )
    (net (code "51") (name "Net-(Q1-C)") (class "Default")
      (node (ref "DS5") (pin "A") (pinfunction "A_A") (pintype "bidirectional"))
      (node (ref "Q1") (pin "3") (pinfunction "C_3") (pintype "bidirectional"))
      (node (ref "R11") (pin "2") (pinfunction "2_2") (pintype "passive"))
    )
    (net (code "52") (name "Net-(Q2-D)") (class "Default")
      (node (ref "Q2") (pin "3") (pinfunction "D_3") (pintype "bidirectional"))
      (node (ref "R18") (pin "2") (pinfunction "2_2") (pintype "passive"))
    )
    (net (code "53") (name "Net-(Q3-D)") (class "Default")
      (node (ref "Q3") (pin "3") (pinfunction "D_3") (pintype "bidirectional"))
      (node (ref "R19") (pin "2") (pinfunction "2_2") (pintype "passive"))
    )
    (net (code "54") (name "Net-(Q4-D)") (class "Default")
      (node (ref "Q4") (pin "3") (pinfunction "D_3") (pintype "bidirectional"))
      (node (ref "R20") (pin "2") (pinfunction "2_2") (pintype "passive"))
    )
    (net (code "55") (name "Net-(Q5-D)") (class "Default")
      (node (ref "Q5") (pin "3") (pinfunction "D_3") (pintype "bidirectional"))
      (node (ref "R24") (pin "2") (pinfunction "2_2") (pintype "passive"))
    )
    (net (code "56") (name "Net-(Q6-D)") (class "Default")
      (node (ref "Q6") (pin "3") (pinfunction "D_3") (pintype "bidirectional"))
      (node (ref "R25") (pin "2") (pinfunction "2_2") (pintype "passive"))
    )
    (net (code "57") (name "Net-(Q7-D)") (class "Default")
      (node (ref "Q7") (pin "3") (pinfunction "D_3") (pintype "bidirectional"))
      (node (ref "R26") (pin "2") (pinfunction "2_2") (pintype "passive"))
    )
    (net (code "58") (name "Net-(Q8-D)") (class "Default")
      (node (ref "Q8") (pin "3") (pinfunction "D_3") (pintype "bidirectional"))
      (node (ref "R30") (pin "2") (pinfunction "2_2") (pintype "passive"))
    )
    (net (code "59") (name "Net-(Q9-D)") (class "Default")
      (node (ref "Q9") (pin "3") (pinfunction "D_3") (pintype "bidirectional"))
      (node (ref "R31") (pin "2") (pinfunction "2_2") (pintype "passive"))
    )
    (net (code "60") (name "Net-(Q10-D)") (class "Default")
      (node (ref "Q10") (pin "3") (pinfunction "D_3") (pintype "bidirectional"))
      (node (ref "R32") (pin "2") (pinfunction "2_2") (pintype "passive"))
    )
    (net (code "61") (name "Net-(Q11-D)") (class "Default")
      (node (ref "LS1") (pin "-") (pinfunction "-_-") (pintype "bidirectional"))
      (node (ref "Q11") (pin "3") (pinfunction "D_3") (pintype "bidirectional"))
    )
    (net (code "62") (name "Net-(Q12-D)") (class "Default")
      (node (ref "Q12") (pin "3") (pinfunction "D_3") (pintype "bidirectional"))
      (node (ref "R37") (pin "2") (pinfunction "2_2") (pintype "passive"))
    )
    (net (code "63") (name "Net-(Q13-D)") (class "Default")
      (node (ref "Q13") (pin "3") (pinfunction "D_3") (pintype "bidirectional"))
      (node (ref "R38") (pin "2") (pinfunction "2_2") (pintype "passive"))
    )
    (net (code "64") (name "Net-(Q14-D)") (class "Default")
      (node (ref "Q14") (pin "3") (pinfunction "D_3") (pintype "bidirectional"))
      (node (ref "R39") (pin "2") (pinfunction "2_2") (pintype "passive"))
    )
    (net (code "65") (name "Net-(R10-Pad2)") (class "Default")
      (node (ref "R10") (pin "2") (pinfunction "2_2") (pintype "passive"))
      (node (ref "S2") (pin "3") (pinfunction "2_3") (pintype "passive"))
      (node (ref "S2") (pin "4") (pinfunction "2_4") (pintype "passive"))
    )
    (net (code "66") (name "Net-(R11-Pad1)") (class "Default")
      (node (ref "R11") (pin "1") (pinfunction "1_1") (pintype "passive"))
      (node (ref "R12") (pin "2") (pinfunction "2_2") (pintype "passive"))
    )
    (net (code "67") (name "Net-(U1-PB6(XTAL1{slash}TOSC1))") (class "Default")
      (node (ref "C1") (pin "1") (pinfunction "1_1") (pintype "passive"))
      (node (ref "U1") (pin "7") (pinfunction "PB6(XTAL1/TOSC1)_7") (pintype "bidirectional"))
      (node (ref "Y1") (pin "1") (pinfunction "1_1") (pintype "bidirectional"))
    )
    (net (code "68") (name "Net-(U1-PB7(XTAL2{slash}TOSC2))") (class "Default")
      (node (ref "C6") (pin "1") (pinfunction "1_1") (pintype "passive"))
      (node (ref "U1") (pin "8") (pinfunction "PB7(XTAL2/TOSC2)_8") (pintype "bidirectional"))
      (node (ref "Y1") (pin "2") (pinfunction "2_2") (pintype "bidirectional"))
    )
    (net (code "69") (name "Net-(U2-V3)") (class "Default")
      (node (ref "C7") (pin "2") (pinfunction "2_2") (pintype "passive"))
      (node (ref "U2") (pin "4") (pinfunction "V3_4") (pintype "bidirectional"))
    )
    (net (code "70") (name "Net-(U3-CTRL)") (class "Default")
      (node (ref "C11") (pin "1") (pinfunction "1_1") (pintype "passive"))
      (node (ref "U3") (pin "5") (pinfunction "CTRL_5") (pintype "bidirectional"))
    )
    (net (code "71") (name "Net-(U3-DIS)") (class "Default")
      (node (ref "R4") (pin "1") (pinfunction "1_1") (pintype "passive"))
      (node (ref "R5") (pin "2") (pinfunction "2_2") (pintype "passive"))
      (node (ref "U3") (pin "7") (pinfunction "DIS_7") (pintype "bidirectional"))
    )
    (net (code "72") (name "Net-(U3-OUT)") (class "Default")
      (node (ref "R9") (pin "1") (pinfunction "1_1") (pintype "passive"))
      (node (ref "U3") (pin "3") (pinfunction "OUT_3") (pintype "bidirectional"))
    )
    (net (code "73") (name "Net-(U3-THR)") (class "Default")
      (node (ref "C9") (pin "1") (pinfunction "1_1") (pintype "passive"))
      (node (ref "R5") (pin "1") (pinfunction "1_1") (pintype "passive"))
      (node (ref "U3") (pin "2") (pinfunction "TRI_2") (pintype "bidirectional"))
      (node (ref "U3") (pin "6") (pinfunction "THR_6") (pintype "bidirectional"))
    )
    (net (code "74") (name "unconnected-(CN1-ID-PadID1)") (class "Default")
      (node (ref "CN1") (pin "ID1") (pinfunction "ID_ID1") (pintype "passive"))
    )
    (net (code "75") (name "unconnected-(JP1-Pad1)") (class "Default")
      (node (ref "JP1") (pin "1") (pinfunction "1_1") (pintype "passive"))
    )
    (net (code "76") (name "unconnected-(U1-ADC6-Pad19)") (class "Default")
      (node (ref "U1") (pin "19") (pinfunction "ADC6_19") (pintype "bidirectional"))
    )
    (net (code "77") (name "unconnected-(U1-ADC7-Pad22)") (class "Default")
      (node (ref "U1") (pin "22") (pinfunction "ADC7_22") (pintype "bidirectional"))
    )
    (net (code "78") (name "unconnected-(U2-CTS#-Pad9)") (class "Default")
      (node (ref "U2") (pin "9") (pinfunction "CTS#_9") (pintype "bidirectional"))
    )
    (net (code "79") (name "unconnected-(U2-DCD#-Pad12)") (class "Default")
      (node (ref "U2") (pin "12") (pinfunction "DCD#_12") (pintype "bidirectional"))
    )
    (net (code "80") (name "unconnected-(U2-DSR#-Pad10)") (class "Default")
      (node (ref "U2") (pin "10") (pinfunction "DSR#_10") (pintype "bidirectional"))
    )
    (net (code "81") (name "unconnected-(U2-RI#-Pad11)") (class "Default")
      (node (ref "U2") (pin "11") (pinfunction "RI#_11") (pintype "bidirectional"))
    )
    (net (code "82") (name "unconnected-(U2-RST-Pad7)") (class "Default")
      (node (ref "U2") (pin "7") (pinfunction "RST_7") (pintype "bidirectional"))
    )
    (net (code "83") (name "unconnected-(U2-RTS#-Pad14)") (class "Default")
      (node (ref "U2") (pin "14") (pinfunction "RTS#_14") (pintype "bidirectional"))
    )
    (net (code "84") (name "unconnected-(U2-TNOW-Pad15)") (class "Default")
      (node (ref "U2") (pin "15") (pinfunction "TNOW_15") (pintype "bidirectional"))
    )
  )
)
